# USBC.net
KiCad netlist of a schematic drawn in Altium Designer
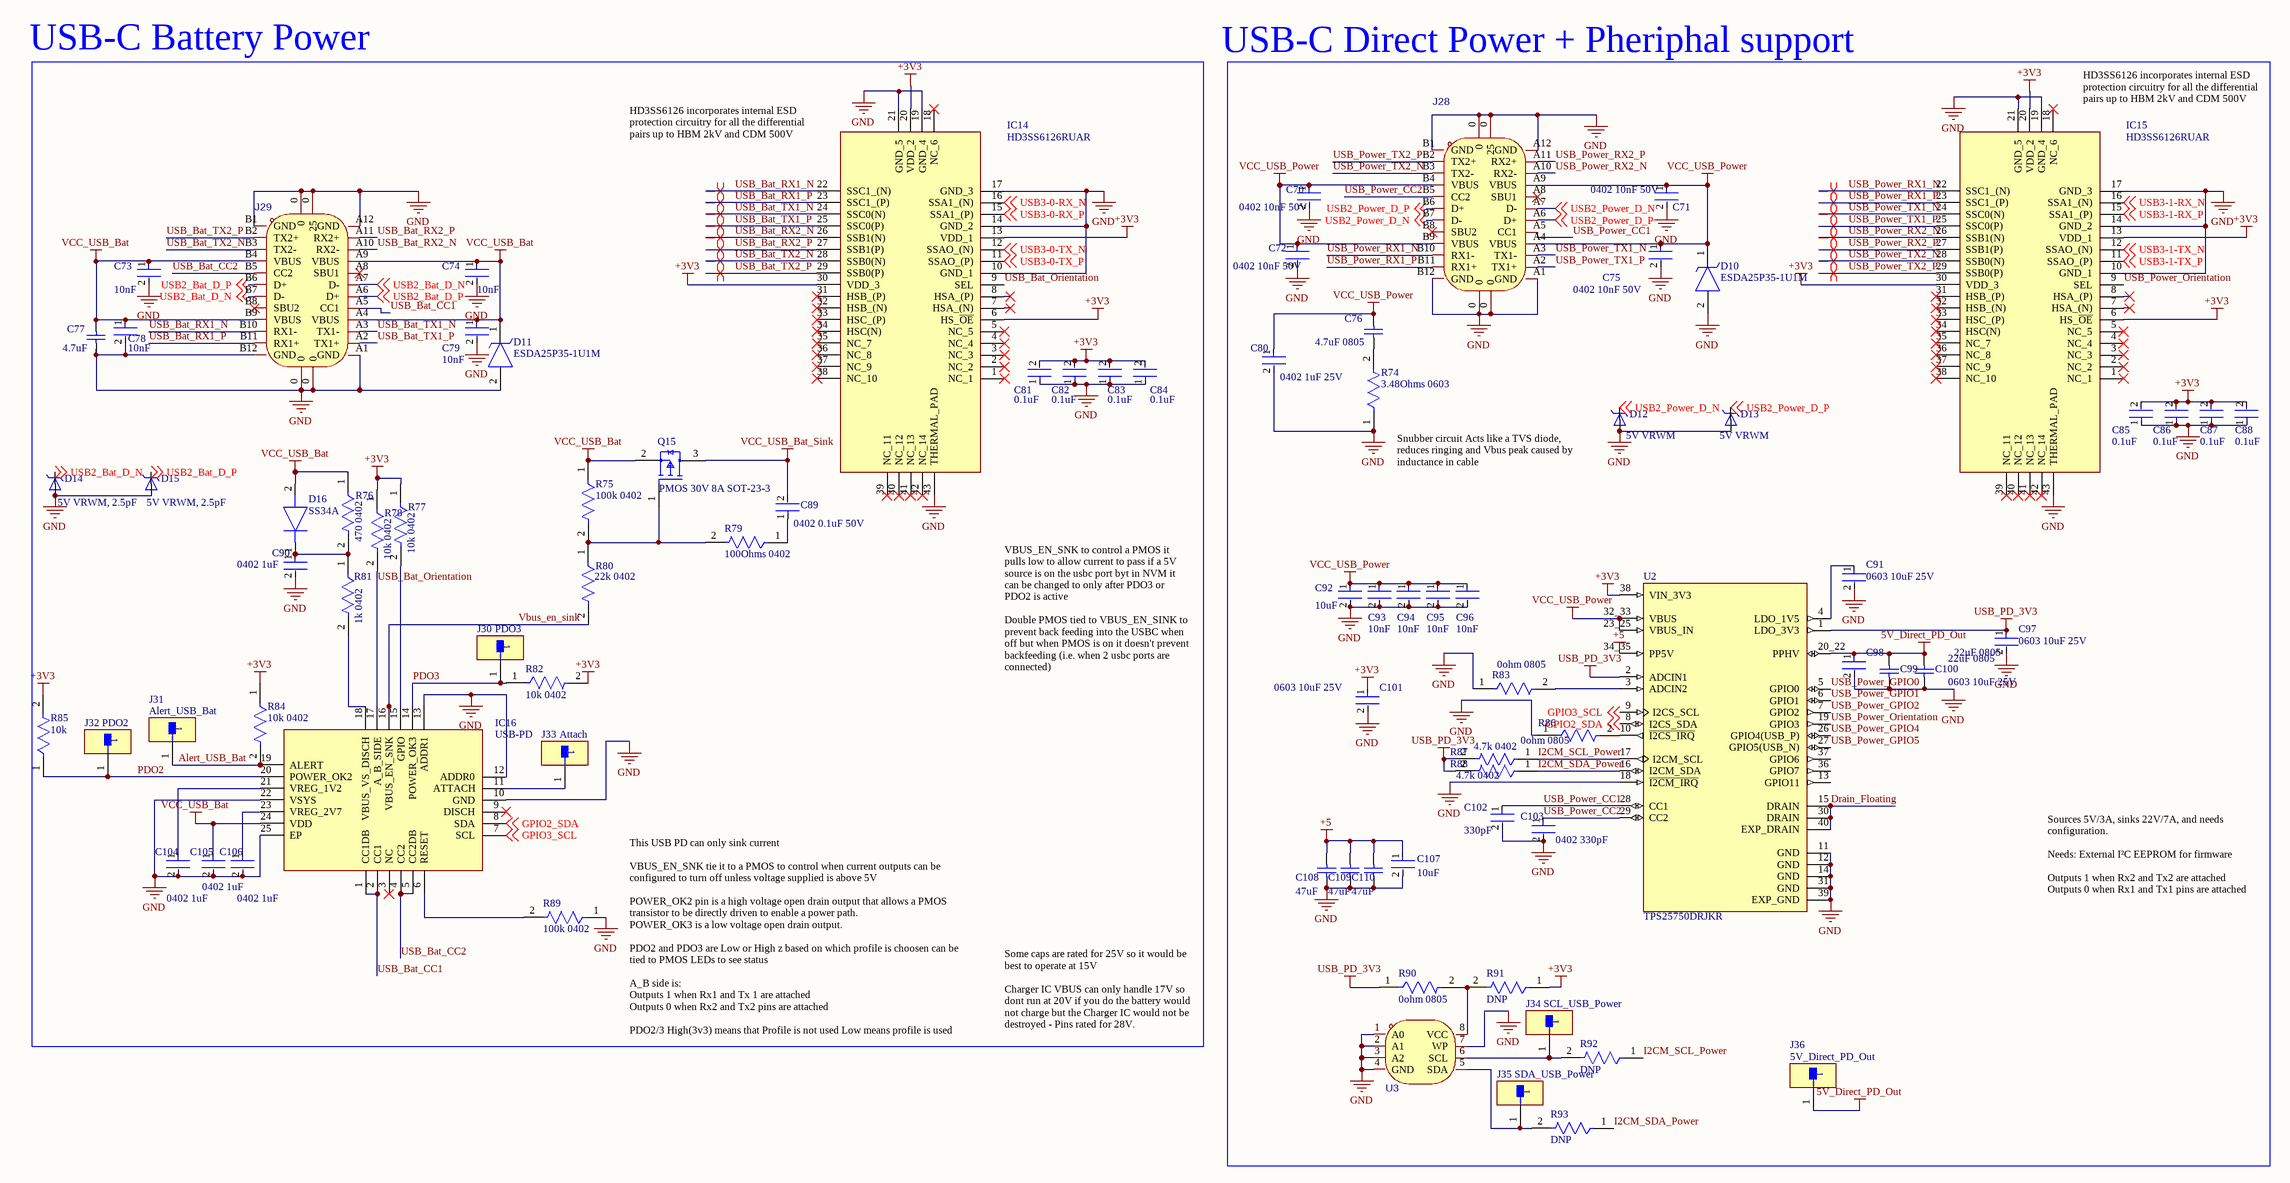
[diagram p0: USBC.SchDoc]

(export (version "E")
  (design (tool "Eeschema 10.0.6"))
  (components
    (comp (ref "C70")
      (value "0402 10nF 50V")
      (footprint "FP-C0402-BB-MFG")
      (description "C15195")
      (fields
        (field (name "TOLERANCE") "0.2")
        (field (name "OCTOPART") "https://octopart.com/c0402c104m3pac7867-kemet-84304880")
      )
      (libsource (lib "Altium Content Vault") (part "b4654b650e69147ec39a6b967a45e02"))
    )
    (comp (ref "C71")
      (value "0402 10nF 50V")
      (footprint "FP-C0402-BB-MFG")
      (description "C15195")
      (fields
        (field (name "TOLERANCE") "0.2")
        (field (name "OCTOPART") "https://octopart.com/c0402c104m3pac7867-kemet-84304880")
      )
      (libsource (lib "Altium Content Vault") (part "b4654b650e69147ec39a6b967a45e02"))
    )
    (comp (ref "C72")
      (value "0402 10nF 50V")
      (footprint "FP-C0402-BB-MFG")
      (description "C15195")
      (fields
        (field (name "TOLERANCE") "0.2")
        (field (name "OCTOPART") "https://octopart.com/c0402c104m3pac7867-kemet-84304880")
      )
      (libsource (lib "Altium Content Vault") (part "b4654b650e69147ec39a6b967a45e02"))
    )
    (comp (ref "C73")
      (value "10nF")
      (footprint "FP-C0402-BB-MFG")
      (description "C15195")
      (fields
        (field (name "TOLERANCE") "0.2")
        (field (name "OCTOPART") "https://octopart.com/c0402c104m3pac7867-kemet-84304880")
      )
      (libsource (lib "Altium Content Vault") (part "b4654b650e69147ec39a6b967a45e02"))
    )
    (comp (ref "C74")
      (value "10nF")
      (footprint "FP-C0402-BB-MFG")
      (description "C15195")
      (fields
        (field (name "TOLERANCE") "0.2")
        (field (name "OCTOPART") "https://octopart.com/c0402c104m3pac7867-kemet-84304880")
      )
      (libsource (lib "Altium Content Vault") (part "b4654b650e69147ec39a6b967a45e02"))
    )
    (comp (ref "C75")
      (value "0402 10nF 50V")
      (footprint "FP-C0402-BB-MFG")
      (description "C15195")
      (fields
        (field (name "TOLERANCE") "0.2")
        (field (name "OCTOPART") "https://octopart.com/c0402c104m3pac7867-kemet-84304880")
      )
      (libsource (lib "Altium Content Vault") (part "b4654b650e69147ec39a6b967a45e02"))
    )
    (comp (ref "C76")
      (value "4.7uF 0805")
      (footprint "CAPC2013X145X50ML20T25")
      (description "C7472970")
      (fields (field (name "MANUFACTURER") "Kemet") (field (name "PART NUMBER") "C0805F223K5RACTU"))
      (libsource (lib "Altium Content Vault") (part "CAP"))
    )
    (comp (ref "C77")
      (value "4.7uF")
      (footprint "CAPC2013X145X50ML20T25")
      (description "C7472970")
      (fields (field (name "MANUFACTURER") "Kemet") (field (name "PART NUMBER") "C0805F223K5RACTU"))
      (libsource (lib "Altium Content Vault") (part "CAP"))
    )
    (comp (ref "C78")
      (value "10nF")
      (footprint "FP-C0402-BB-MFG")
      (description "C15195")
      (fields
        (field (name "TOLERANCE") "0.2")
        (field (name "OCTOPART") "https://octopart.com/c0402c104m3pac7867-kemet-84304880")
      )
      (libsource (lib "Altium Content Vault") (part "b4654b650e69147ec39a6b967a45e02"))
    )
    (comp (ref "C79")
      (value "10nF")
      (footprint "FP-C0402-BB-MFG")
      (description "C15195")
      (fields
        (field (name "TOLERANCE") "0.2")
        (field (name "OCTOPART") "https://octopart.com/c0402c104m3pac7867-kemet-84304880")
      )
      (libsource (lib "Altium Content Vault") (part "b4654b650e69147ec39a6b967a45e02"))
    )
    (comp (ref "C80")
      (value "0402 1uF 25V")
      (footprint "FP-C0402-BB-MFG")
      (description "C52923")
      (fields
        (field (name "TOLERANCE") "0.2")
        (field (name "OCTOPART") "https://octopart.com/c0402c104m3pac7867-kemet-84304880")
      )
      (libsource (lib "Altium Content Vault") (part "b4654b650e69147ec39a6b967a45e02"))
    )
    (comp (ref "C81")
      (value "0.1uF")
      (footprint "FP-C0402-BB-MFG")
      (description "C307331")
      (fields
        (field (name "TOLERANCE") "0.2")
        (field (name "OCTOPART") "https://octopart.com/c0402c104m3pac7867-kemet-84304880")
      )
      (libsource (lib "Altium Content Vault") (part "b4654b650e69147ec39a6b967a45e02"))
    )
    (comp (ref "C82")
      (value "0.1uF")
      (footprint "FP-C0402-BB-MFG")
      (description "C307331")
      (fields
        (field (name "TOLERANCE") "0.2")
        (field (name "OCTOPART") "https://octopart.com/c0402c104m3pac7867-kemet-84304880")
      )
      (libsource (lib "Altium Content Vault") (part "b4654b650e69147ec39a6b967a45e02"))
    )
    (comp (ref "C83")
      (value "0.1uF")
      (footprint "FP-C0402-BB-MFG")
      (description "C307331")
      (fields
        (field (name "TOLERANCE") "0.2")
        (field (name "OCTOPART") "https://octopart.com/c0402c104m3pac7867-kemet-84304880")
      )
      (libsource (lib "Altium Content Vault") (part "b4654b650e69147ec39a6b967a45e02"))
    )
    (comp (ref "C84")
      (value "0.1uF")
      (footprint "FP-C0402-BB-MFG")
      (description "C307331")
      (fields
        (field (name "TOLERANCE") "0.2")
        (field (name "OCTOPART") "https://octopart.com/c0402c104m3pac7867-kemet-84304880")
      )
      (libsource (lib "Altium Content Vault") (part "b4654b650e69147ec39a6b967a45e02"))
    )
    (comp (ref "C85")
      (value "0.1uF")
      (footprint "FP-C0402-BB-MFG")
      (description "C307331")
      (fields
        (field (name "TOLERANCE") "0.2")
        (field (name "OCTOPART") "https://octopart.com/c0402c104m3pac7867-kemet-84304880")
      )
      (libsource (lib "Altium Content Vault") (part "b4654b650e69147ec39a6b967a45e02"))
    )
    (comp (ref "C86")
      (value "0.1uF")
      (footprint "FP-C0402-BB-MFG")
      (description "C307331")
      (fields
        (field (name "TOLERANCE") "0.2")
        (field (name "OCTOPART") "https://octopart.com/c0402c104m3pac7867-kemet-84304880")
      )
      (libsource (lib "Altium Content Vault") (part "b4654b650e69147ec39a6b967a45e02"))
    )
    (comp (ref "C87")
      (value "0.1uF")
      (footprint "FP-C0402-BB-MFG")
      (description "C307331")
      (fields
        (field (name "TOLERANCE") "0.2")
        (field (name "OCTOPART") "https://octopart.com/c0402c104m3pac7867-kemet-84304880")
      )
      (libsource (lib "Altium Content Vault") (part "b4654b650e69147ec39a6b967a45e02"))
    )
    (comp (ref "C88")
      (value "0.1uF")
      (footprint "FP-C0402-BB-MFG")
      (description "C307331")
      (fields
        (field (name "TOLERANCE") "0.2")
        (field (name "OCTOPART") "https://octopart.com/c0402c104m3pac7867-kemet-84304880")
      )
      (libsource (lib "Altium Content Vault") (part "b4654b650e69147ec39a6b967a45e02"))
    )
    (comp (ref "C89")
      (value "0402 0.1uF 50V")
      (footprint "FP-C0402-BB-MFG")
      (description "C307331")
      (fields
        (field (name "TOLERANCE") "0.2")
        (field (name "OCTOPART") "https://octopart.com/c0402c104m3pac7867-kemet-84304880")
      )
      (libsource (lib "Altium Content Vault") (part "b4654b650e69147ec39a6b967a45e02"))
    )
    (comp (ref "C90")
      (value "0402 1uF")
      (footprint "FP-C0402-BB-MFG")
      (description "C52923")
      (fields
        (field (name "TOLERANCE") "0.2")
        (field (name "OCTOPART") "https://octopart.com/c0402c104m3pac7867-kemet-84304880")
      )
      (libsource (lib "Altium Content Vault") (part "b4654b650e69147ec39a6b967a45e02"))
    )
    (comp (ref "C91")
      (value "0603 10uF 25V")
      (footprint "FP-CC0603-DC-MFG")
      (description "C96446")
      (fields (field (name "TOLERANCE") "10%"))
      (libsource (lib "Altium Content Vault") (part "b4654b650e69147ec39a6b967a45e02"))
    )
    (comp (ref "C92")
      (value "10uF")
      (footprint "FP-CC0603-DC-MFG")
      (description "C96446")
      (fields (field (name "TOLERANCE") "10%"))
      (libsource (lib "Altium Content Vault") (part "b4654b650e69147ec39a6b967a45e02"))
    )
    (comp (ref "C93")
      (value "10nF")
      (footprint "FP-C0402-BB-MFG")
      (description "C15195")
      (fields
        (field (name "TOLERANCE") "0.2")
        (field (name "OCTOPART") "https://octopart.com/c0402c104m3pac7867-kemet-84304880")
      )
      (libsource (lib "Altium Content Vault") (part "b4654b650e69147ec39a6b967a45e02"))
    )
    (comp (ref "C94")
      (value "10nF")
      (footprint "FP-C0402-BB-MFG")
      (description "C15195")
      (fields
        (field (name "TOLERANCE") "0.2")
        (field (name "OCTOPART") "https://octopart.com/c0402c104m3pac7867-kemet-84304880")
      )
      (libsource (lib "Altium Content Vault") (part "b4654b650e69147ec39a6b967a45e02"))
    )
    (comp (ref "C95")
      (value "10nF")
      (footprint "FP-C0402-BB-MFG")
      (description "C15195")
      (fields
        (field (name "TOLERANCE") "0.2")
        (field (name "OCTOPART") "https://octopart.com/c0402c104m3pac7867-kemet-84304880")
      )
      (libsource (lib "Altium Content Vault") (part "b4654b650e69147ec39a6b967a45e02"))
    )
    (comp (ref "C96")
      (value "10nF")
      (footprint "FP-C0402-BB-MFG")
      (description "C15195")
      (fields
        (field (name "TOLERANCE") "0.2")
        (field (name "OCTOPART") "https://octopart.com/c0402c104m3pac7867-kemet-84304880")
      )
      (libsource (lib "Altium Content Vault") (part "b4654b650e69147ec39a6b967a45e02"))
    )
    (comp (ref "C97")
      (value "0603 10uF 25V")
      (footprint "FP-CC0603-DC-MFG")
      (description "C96446")
      (fields (field (name "TOLERANCE") "10%"))
      (libsource (lib "Altium Content Vault") (part "b4654b650e69147ec39a6b967a45e02"))
    )
    (comp (ref "C98")
      (value "0603 10uF 25V")
      (footprint "FP-CC0603-DC-MFG")
      (description "C96446")
      (fields (field (name "TOLERANCE") "10%"))
      (libsource (lib "Altium Content Vault") (part "b4654b650e69147ec39a6b967a45e02"))
    )
    (comp (ref "C99")
      (value "22uF 0805")
      (footprint "CAPC2013X94X50LL20T25")
      (description "C45783")
      (fields
        (field (name "PART NUMBER") "08051C102KAT4A")
        (field (name "MANUFACTURER") "AVX Interconnect / Elco")
      )
      (libsource (lib "Altium Content Vault") (part "CAP"))
    )
    (comp (ref "C100")
      (value "22uF 0805")
      (footprint "CAPC2013X94X50LL20T25")
      (description "C45783")
      (fields
        (field (name "PART NUMBER") "08051C102KAT4A")
        (field (name "MANUFACTURER") "AVX Interconnect / Elco")
      )
      (libsource (lib "Altium Content Vault") (part "CAP"))
    )
    (comp (ref "C101")
      (value "0603 10uF 25V")
      (footprint "FP-CC0603-DC-MFG")
      (description "C96446")
      (fields (field (name "TOLERANCE") "10%"))
      (libsource (lib "Altium Content Vault") (part "b4654b650e69147ec39a6b967a45e02"))
    )
    (comp (ref "C102")
      (value "330pF")
      (footprint "FP-C0402-BB-MFG")
      (description "C13533")
      (fields
        (field (name "TOLERANCE") "0.2")
        (field (name "OCTOPART") "https://octopart.com/c0402c104m3pac7867-kemet-84304880")
      )
      (libsource (lib "Altium Content Vault") (part "b4654b650e69147ec39a6b967a45e02"))
    )
    (comp (ref "C103")
      (value "0402 330pF")
      (footprint "FP-C0402-BB-MFG")
      (description "C13533")
      (fields
        (field (name "TOLERANCE") "0.2")
        (field (name "OCTOPART") "https://octopart.com/c0402c104m3pac7867-kemet-84304880")
      )
      (libsource (lib "Altium Content Vault") (part "b4654b650e69147ec39a6b967a45e02"))
    )
    (comp (ref "C104")
      (value "0402 1uF")
      (footprint "FP-C0402-BB-MFG")
      (description "C52923")
      (fields
        (field (name "TOLERANCE") "0.2")
        (field (name "OCTOPART") "https://octopart.com/c0402c104m3pac7867-kemet-84304880")
      )
      (libsource (lib "Altium Content Vault") (part "b4654b650e69147ec39a6b967a45e02"))
    )
    (comp (ref "C105")
      (value "0402 1uF")
      (footprint "FP-C0402-BB-MFG")
      (description "C52923")
      (fields
        (field (name "TOLERANCE") "0.2")
        (field (name "OCTOPART") "https://octopart.com/c0402c104m3pac7867-kemet-84304880")
      )
      (libsource (lib "Altium Content Vault") (part "b4654b650e69147ec39a6b967a45e02"))
    )
    (comp (ref "C106")
      (value "0402 1uF")
      (footprint "FP-C0402-BB-MFG")
      (description "C52923")
      (fields
        (field (name "TOLERANCE") "0.2")
        (field (name "OCTOPART") "https://octopart.com/c0402c104m3pac7867-kemet-84304880")
      )
      (libsource (lib "Altium Content Vault") (part "b4654b650e69147ec39a6b967a45e02"))
    )
    (comp (ref "C107")
      (value "10uF")
      (footprint "FP-CC0603-DC-MFG")
      (description "C96446")
      (fields (field (name "TOLERANCE") "10%"))
      (libsource (lib "Altium Content Vault") (part "b4654b650e69147ec39a6b967a45e02"))
    )
    (comp (ref "C108")
      (value "47uF")
      (footprint "CAPC1206(3216)100_N")
      (description "C7472975")
      (fields (field (name "TOLERANCE") "Â±1%"))
      (libsource (lib "Altium Content Vault") (part "CAP"))
    )
    (comp (ref "C109")
      (value "47uF")
      (footprint "CAPC1206(3216)100_N")
      (description "C7472975")
      (fields (field (name "TOLERANCE") "Â±1%"))
      (libsource (lib "Altium Content Vault") (part "CAP"))
    )
    (comp (ref "C110")
      (value "47uF")
      (footprint "CAPC1206(3216)100_N")
      (description "C7472975")
      (fields (field (name "TOLERANCE") "Â±1%"))
      (libsource (lib "Altium Content Vault") (part "CAP"))
    )
    (comp (ref "D10")
      (value "ESDA25P35-1U1M")
      (footprint "PcbLib1:ESDA25P351U1M")
      (description "C1974707")
      (fields (field (name "MOUSER PART NUMBER") "511-ESDA25P35-1U1M"))
      (libsource (lib "*") (part "ESDA25P35-1U1M"))
    )
    (comp (ref "D11")
      (value "ESDA25P35-1U1M")
      (footprint "PcbLib1:ESDA25P351U1M")
      (description "C1974707")
      (fields (field (name "MOUSER PART NUMBER") "511-ESDA25P35-1U1M"))
      (libsource (lib "*") (part "ESDA25P35-1U1M"))
    )
    (comp (ref "D12")
      (value "5V VRWM")
      (footprint "PcbLib1:SODFL1060X40N")
      (description "C242267")
      (fields (field (name "MF") "ON Semiconductor") (field (name "MP") "ESD9M5.0ST5G"))
      (libsource (lib "Schlib1") (part "ESD9M5.0ST5G"))
    )
    (comp (ref "D13")
      (value "5V VRWM")
      (footprint "PcbLib1:SODFL1060X40N")
      (description "C242267")
      (fields (field (name "MF") "ON Semiconductor") (field (name "MP") "ESD9M5.0ST5G"))
      (libsource (lib "Schlib1") (part "ESD9M5.0ST5G"))
    )
    (comp (ref "D14")
      (value "5V VRWM, 2.5pF")
      (footprint "PcbLib1:SODFL1060X40N")
      (description "C242267")
      (fields (field (name "MF") "ON Semiconductor") (field (name "MP") "ESD9M5.0ST5G"))
      (libsource (lib "Schlib1") (part "ESD9M5.0ST5G"))
    )
    (comp (ref "D15")
      (value "5V VRWM, 2.5pF")
      (footprint "PcbLib1:SODFL1060X40N")
      (description "C242267")
      (fields (field (name "MF") "ON Semiconductor") (field (name "MP") "ESD9M5.0ST5G"))
      (libsource (lib "Schlib1") (part "ESD9M5.0ST5G"))
    )
    (comp (ref "D16")
      (value "SS34A")
      (footprint "SamacSys:DIOM5026X262N")
      (description "C8678")
      (libsource (lib "*") (part "SS34A"))
    )
    (comp (ref "IC14")
      (value "HD3SS6126RUAR")
      (footprint "PcbLib1:QFN50P350X900X80-43N-D")
      (description "C701818")
      (fields (field (name "MOUSER PART NUMBER") "595-HD3SS6126RUAR"))
      (libsource (lib "*") (part "HD3SS6126RUAR"))
    )
    (comp (ref "IC15")
      (value "HD3SS6126RUAR")
      (footprint "PcbLib1:QFN50P350X900X80-43N-D")
      (description "C701818")
      (fields (field (name "MOUSER PART NUMBER") "595-HD3SS6126RUAR"))
      (libsource (lib "*") (part "HD3SS6126RUAR"))
    )
    (comp (ref "IC16")
      (value "USB-PD")
      (footprint "PcbLib1:QFN50P400X400X100-25N-D")
      (description "C2678061")
      (fields
        (field (name "MANUFACTURER_PART_NUMBER") "STUSB4500QTR")
        (field (name "MOUSER PART NUMBER") "511-STUSB4500QTR")
      )
      (libsource (lib "Schlib1") (part "STUSB4500QTR"))
    )
    (comp (ref "J28")
      (value "1054500101")
      (footprint "USB-C-SMD_TYPE-C-USB-18")
      (description "C134092")
      (fields (field (name "MANUFACTURER") "MOLEX"))
      (libsource (lib "Schlib1") (part "1054500101"))
    )
    (comp (ref "J29")
      (value "1054500101")
      (footprint "USB-C-SMD_TYPE-C-USB-18")
      (description "C134092")
      (fields (field (name "MANUFACTURER") "MOLEX"))
      (libsource (lib "Schlib1") (part "1054500101"))
    )
    (comp (ref "J30")
      (value "PDO3")
      (footprint "FP-5015-MFG")
      (description "PC TEST POINT MINIATURE")
      (fields (field (name "MANUFACTURER PART NUMBER") "5015") (field (name "MANUFACTURER") "keystone"))
      (libsource (lib "Altium Content Vault") (part "dd45045ce8184df9e99e12baf3f412c"))
    )
    (comp (ref "J31")
      (value "Alert_USB_Bat")
      (footprint "FP-5015-MFG")
      (description "PC TEST POINT MINIATURE")
      (fields (field (name "MANUFACTURER PART NUMBER") "5015") (field (name "MANUFACTURER") "keystone"))
      (libsource (lib "Altium Content Vault") (part "dd45045ce8184df9e99e12baf3f412c"))
    )
    (comp (ref "J32")
      (value "PDO2")
      (footprint "FP-5015-MFG")
      (description "PC TEST POINT MINIATURE")
      (fields (field (name "MANUFACTURER PART NUMBER") "5015") (field (name "MANUFACTURER") "keystone"))
      (libsource (lib "Altium Content Vault") (part "dd45045ce8184df9e99e12baf3f412c"))
    )
    (comp (ref "J33")
      (value "Attach")
      (footprint "FP-5015-MFG")
      (description "PC TEST POINT MINIATURE")
      (fields (field (name "MANUFACTURER PART NUMBER") "5015") (field (name "MANUFACTURER") "keystone"))
      (libsource (lib "Altium Content Vault") (part "dd45045ce8184df9e99e12baf3f412c"))
    )
    (comp (ref "J34")
      (value "SCL_USB_Power")
      (footprint "FP-TSW-101-07-L-S-MFG")
      (description "CONN HEADER VERT 1POS")
      (libsource (lib "Altium Content Vault") (part "dd45045ce8184df9e99e12baf3f412c"))
    )
    (comp (ref "J35")
      (value "SDA_USB_Power")
      (footprint "FP-TSW-101-07-L-S-MFG")
      (description "CONN HEADER VERT 1POS")
      (libsource (lib "Altium Content Vault") (part "dd45045ce8184df9e99e12baf3f412c"))
    )
    (comp (ref "J36")
      (value "5V_Direct_PD_Out")
      (footprint "FP-5015-MFG")
      (description "PC TEST POINT MINIATURE")
      (fields (field (name "MANUFACTURER PART NUMBER") "5015") (field (name "MANUFACTURER") "keystone"))
      (libsource (lib "Altium Content Vault") (part "dd45045ce8184df9e99e12baf3f412c"))
    )
    (comp (ref "Q15")
      (value "PMOS 30V 8A SOT-23-3")
      (footprint "FP-SOT23-MFG")
      (description "C48934562")
      (fields
        (field (name "MANUFACTURER") "Diodes Inc.")
        (field (name "MANUFACTURER PART NUMBER") "DMG2305UX-13")
      )
      (libsource (lib "Altium Content Vault") (part "b298ed0aef6ca29edb293456b19cad3"))
    )
    (comp (ref "R74")
      (value "3.48Ohms 0603")
      (footprint "FP-RMCF0603-IPC_A")
      (description "C322150")
      (fields (field (name "TOLERANCE") "1%"))
      (libsource (lib "Altium Content Vault") (part "1029c3af85768c4190bb7ad29bc67b5"))
    )
    (comp (ref "R75")
      (value "100k 0402")
      (footprint "FP-RMCF0402-MFG")
      (description "C25741")
      (fields (field (name "TOLERANCE") "5%"))
      (libsource (lib "Altium Content Vault") (part "1029c3af85768c4190bb7ad29bc67b5"))
    )
    (comp (ref "R76")
      (value "470 0402")
      (footprint "FP-RMCF0402-MFG")
      (description "C25117")
      (fields (field (name "TOLERANCE") "5%"))
      (libsource (lib "Altium Content Vault") (part "1029c3af85768c4190bb7ad29bc67b5"))
    )
    (comp (ref "R77")
      (value "10k 0402")
      (footprint "FP-RMCF0402-MFG")
      (description "C25744")
      (fields (field (name "TOLERANCE") "5%"))
      (libsource (lib "Altium Content Vault") (part "1029c3af85768c4190bb7ad29bc67b5"))
    )
    (comp (ref "R78")
      (value "10k 0402")
      (footprint "FP-RMCF0402-MFG")
      (description "C25744")
      (fields (field (name "TOLERANCE") "5%"))
      (libsource (lib "Altium Content Vault") (part "1029c3af85768c4190bb7ad29bc67b5"))
    )
    (comp (ref "R79")
      (value "100Ohms 0402")
      (footprint "FP-RMCF0402-MFG")
      (description "C25076")
      (fields (field (name "TOLERANCE") "5%"))
      (libsource (lib "Altium Content Vault") (part "1029c3af85768c4190bb7ad29bc67b5"))
    )
    (comp (ref "R80")
      (value "22k 0402")
      (footprint "FP-RMCF0402-MFG")
      (description "C25768")
      (fields (field (name "TOLERANCE") "5%"))
      (libsource (lib "Altium Content Vault") (part "1029c3af85768c4190bb7ad29bc67b5"))
    )
    (comp (ref "R81")
      (value "1k 0402")
      (footprint "FP-RMCF0402-MFG")
      (description "C11702")
      (fields (field (name "TOLERANCE") "5%"))
      (libsource (lib "Altium Content Vault") (part "1029c3af85768c4190bb7ad29bc67b5"))
    )
    (comp (ref "R82")
      (value "10k 0402")
      (footprint "FP-RMCF0402-MFG")
      (description "C25744")
      (fields (field (name "TOLERANCE") "5%"))
      (libsource (lib "Altium Content Vault") (part "1029c3af85768c4190bb7ad29bc67b5"))
    )
    (comp (ref "R83")
      (value "0ohm 0805")
      (footprint "FP-RN73R2A-IPC_C")
      (description "C17477")
      (libsource (lib "Altium Content Vault") (part "1029c3af85768c4190bb7ad29bc67b5"))
    )
    (comp (ref "R84")
      (value "10k 0402")
      (footprint "FP-RMCF0402-MFG")
      (description "C25744")
      (fields (field (name "TOLERANCE") "5%"))
      (libsource (lib "Altium Content Vault") (part "1029c3af85768c4190bb7ad29bc67b5"))
    )
    (comp (ref "R85")
      (value "10k")
      (footprint "FP-RMCF0402-MFG")
      (description "C25744")
      (fields (field (name "TOLERANCE") "5%"))
      (libsource (lib "Altium Content Vault") (part "1029c3af85768c4190bb7ad29bc67b5"))
    )
    (comp (ref "R86")
      (value "0ohm 0805")
      (footprint "FP-RN73R2A-IPC_C")
      (description "C17477")
      (libsource (lib "Altium Content Vault") (part "1029c3af85768c4190bb7ad29bc67b5"))
    )
    (comp (ref "R87")
      (value "4.7k 0402")
      (footprint "FP-RMCF0402-MFG")
      (description "C25900")
      (fields (field (name "TOLERANCE") "5%"))
      (libsource (lib "Altium Content Vault") (part "1029c3af85768c4190bb7ad29bc67b5"))
    )
    (comp (ref "R88")
      (value "4.7k 0402")
      (footprint "FP-RMCF0402-MFG")
      (description "C25900")
      (fields (field (name "TOLERANCE") "5%"))
      (libsource (lib "Altium Content Vault") (part "1029c3af85768c4190bb7ad29bc67b5"))
    )
    (comp (ref "R89")
      (value "100k 0402")
      (footprint "FP-RMCF0402-MFG")
      (description "C25741")
      (fields (field (name "TOLERANCE") "5%"))
      (libsource (lib "Altium Content Vault") (part "1029c3af85768c4190bb7ad29bc67b5"))
    )
    (comp (ref "R90")
      (value "0ohm 0805")
      (footprint "FP-RN73R2A-IPC_C")
      (description "C17477")
      (libsource (lib "Altium Content Vault") (part "1029c3af85768c4190bb7ad29bc67b5"))
    )
    (comp (ref "R91")
      (value "DNP")
      (footprint "FP-RN73R2A-IPC_C")
      (description "DNP 0805")
      (libsource (lib "Altium Content Vault") (part "1029c3af85768c4190bb7ad29bc67b5"))
    )
    (comp (ref "R92")
      (value "DNP")
      (footprint "FP-RN73R2A-IPC_C")
      (description "DNP 0805")
      (libsource (lib "Altium Content Vault") (part "1029c3af85768c4190bb7ad29bc67b5"))
    )
    (comp (ref "R93")
      (value "DNP")
      (footprint "FP-RN73R2A-IPC_C")
      (description "DNP 0805")
      (libsource (lib "Altium Content Vault") (part "1029c3af85768c4190bb7ad29bc67b5"))
    )
    (comp (ref "U2")
      (value "TPS25750DRJKR")
      (footprint "IC_TPS25750DRJKR")
      (description "C2868209")
      (fields (field (name "MF") "Texas Instruments"))
      (libsource (lib "Schlib1") (part "TPS25750DRJKR"))
    )
    (comp (ref "U3")
      (value "BL24C256A-SFRC")
      (footprint "TSSOP-8_L4.4-W3.0-P0.65-LS6.4-BL")
      (description "C110276")
      (fields (field (name "MANUFACTURER") "BL(上海贝岭)"))
      (libsource (lib "Schlib1") (part "BL24C256A-SFRC"))
    )
  )
  (nets
    (net (code "1") (name "+3V3") (class "Default")
      (node (ref "C101") (pin "1") (pinfunction "1_1") (pintype "passive"))
      (node (ref "C81") (pin "2") (pinfunction "2_2") (pintype "passive"))
      (node (ref "C82") (pin "2") (pinfunction "2_2") (pintype "passive"))
      (node (ref "C83") (pin "2") (pinfunction "2_2") (pintype "passive"))
      (node (ref "C84") (pin "2") (pinfunction "2_2") (pintype "passive"))
      (node (ref "C85") (pin "2") (pinfunction "2_2") (pintype "passive"))
      (node (ref "C86") (pin "2") (pinfunction "2_2") (pintype "passive"))
      (node (ref "C87") (pin "2") (pinfunction "2_2") (pintype "passive"))
      (node (ref "C88") (pin "2") (pinfunction "2_2") (pintype "passive"))
      (node (ref "IC14") (pin "13") (pinfunction "VDD_1_13") (pintype "passive"))
      (node (ref "IC14") (pin "20") (pinfunction "VDD_2_20") (pintype "passive"))
      (node (ref "IC14") (pin "30") (pinfunction "VDD_3_30") (pintype "passive"))
      (node (ref "IC14") (pin "6") (pinfunction "HS_~{OE}_6") (pintype "passive"))
      (node (ref "IC15") (pin "13") (pinfunction "VDD_1_13") (pintype "passive"))
      (node (ref "IC15") (pin "20") (pinfunction "VDD_2_20") (pintype "passive"))
      (node (ref "IC15") (pin "30") (pinfunction "VDD_3_30") (pintype "passive"))
      (node (ref "IC15") (pin "6") (pinfunction "HS_~{OE}_6") (pintype "passive"))
      (node (ref "R77") (pin "1") (pinfunction "1_1") (pintype "passive"))
      (node (ref "R78") (pin "1") (pinfunction "1_1") (pintype "passive"))
      (node (ref "R82") (pin "2") (pinfunction "2_2") (pintype "passive"))
      (node (ref "R84") (pin "1") (pinfunction "1_1") (pintype "passive"))
      (node (ref "R85") (pin "2") (pinfunction "2_2") (pintype "passive"))
      (node (ref "R91") (pin "1") (pinfunction "1_1") (pintype "passive"))
      (node (ref "U2") (pin "38") (pinfunction "VIN_3V3_38") (pintype "input"))
    )
    (net (code "2") (name "+5") (class "Default")
      (node (ref "C107") (pin "1") (pinfunction "1_1") (pintype "passive"))
      (node (ref "C108") (pin "2") (pinfunction "2_2") (pintype "passive"))
      (node (ref "C109") (pin "2") (pinfunction "2_2") (pintype "passive"))
      (node (ref "C110") (pin "2") (pinfunction "2_2") (pintype "passive"))
      (node (ref "U2") (pin "34_35") (pinfunction "PP5V_34_35") (pintype "input"))
    )
    (net (code "3") (name "/Alert_USB_Bat") (class "Default")
      (node (ref "IC16") (pin "19") (pinfunction "ALERT_19") (pintype "passive"))
      (node (ref "J31") (pin "1") (pinfunction "1_1") (pintype "passive"))
      (node (ref "R84") (pin "2") (pinfunction "2_2") (pintype "passive"))
    )
    (net (code "4") (name "/Drain_Floating") (class "Default")
      (node (ref "U2") (pin "15") (pinfunction "DRAIN_15") (pintype "passive"))
      (node (ref "U2") (pin "30") (pinfunction "DRAIN_30") (pintype "passive"))
      (node (ref "U2") (pin "40") (pinfunction "EXP_DRAIN_40") (pintype "passive"))
    )
    (net (code "5") (name "/I2CM_SCL_Power") (class "Default")
      (node (ref "R87") (pin "1") (pinfunction "1_1") (pintype "passive"))
      (node (ref "R92") (pin "1") (pinfunction "1_1") (pintype "passive"))
      (node (ref "U2") (pin "17") (pinfunction "I2CM_SCL_17") (pintype "output"))
    )
    (net (code "6") (name "/I2CM_SDA_Power") (class "Default")
      (node (ref "R88") (pin "1") (pinfunction "1_1") (pintype "passive"))
      (node (ref "R93") (pin "1") (pinfunction "1_1") (pintype "passive"))
      (node (ref "U2") (pin "16") (pinfunction "I2CM_SDA_16") (pintype "bidirectional"))
    )
    (net (code "7") (name "/PDO2") (class "Default")
      (node (ref "IC16") (pin "20") (pinfunction "POWER_OK2_20") (pintype "passive"))
      (node (ref "J32") (pin "1") (pinfunction "1_1") (pintype "passive"))
      (node (ref "R85") (pin "1") (pinfunction "1_1") (pintype "passive"))
    )
    (net (code "8") (name "/PDO3") (class "Default")
      (node (ref "IC16") (pin "14") (pinfunction "POWER_OK3_14") (pintype "passive"))
      (node (ref "J30") (pin "1") (pinfunction "1_1") (pintype "passive"))
      (node (ref "R82") (pin "1") (pinfunction "1_1") (pintype "passive"))
    )
    (net (code "9") (name "/USB_Bat_CC1") (class "Default")
      (node (ref "IC16") (pin "1") (pinfunction "CC1DB_1") (pintype "passive"))
      (node (ref "IC16") (pin "2") (pinfunction "CC1_2") (pintype "passive"))
      (node (ref "J29") (pin "A5") (pinfunction "CC1_A5") (pintype "passive"))
    )
    (net (code "10") (name "/USB_Bat_CC2") (class "Default")
      (node (ref "IC16") (pin "4") (pinfunction "CC2_4") (pintype "passive"))
      (node (ref "IC16") (pin "5") (pinfunction "CC2DB_5") (pintype "passive"))
      (node (ref "J29") (pin "B5") (pinfunction "CC2_B5") (pintype "passive"))
    )
    (net (code "11") (name "/USB_Bat_Orientation") (class "Default")
      (node (ref "IC14") (pin "9") (pinfunction "SEL_9") (pintype "passive"))
      (node (ref "IC16") (pin "17") (pinfunction "A_B_SIDE_17") (pintype "passive"))
      (node (ref "R78") (pin "2") (pinfunction "2_2") (pintype "passive"))
    )
    (net (code "12") (name "/USB_Bat_RX1_N") (class "Default")
      (node (ref "IC14") (pin "22") (pinfunction "SSC1_(N)_22") (pintype "passive"))
      (node (ref "J29") (pin "B10") (pinfunction "RX1-_B10") (pintype "passive"))
    )
    (net (code "13") (name "/USB_Bat_RX1_P") (class "Default")
      (node (ref "IC14") (pin "23") (pinfunction "SSC1_(P)_23") (pintype "passive"))
      (node (ref "J29") (pin "B11") (pinfunction "RX1+_B11") (pintype "passive"))
    )
    (net (code "14") (name "/USB_Bat_RX2_N") (class "Default")
      (node (ref "IC14") (pin "26") (pinfunction "SSB1(N)_26") (pintype "passive"))
      (node (ref "J29") (pin "A10") (pinfunction "RX2-_A10") (pintype "passive"))
    )
    (net (code "15") (name "/USB_Bat_RX2_P") (class "Default")
      (node (ref "IC14") (pin "27") (pinfunction "SSB1(P)_27") (pintype "passive"))
      (node (ref "J29") (pin "A11") (pinfunction "RX2+_A11") (pintype "passive"))
    )
    (net (code "16") (name "/USB_Bat_TX1_N") (class "Default")
      (node (ref "IC14") (pin "24") (pinfunction "SSC0(N)_24") (pintype "passive"))
      (node (ref "J29") (pin "A3") (pinfunction "TX1-_A3") (pintype "passive"))
    )
    (net (code "17") (name "/USB_Bat_TX1_P") (class "Default")
      (node (ref "IC14") (pin "25") (pinfunction "SSC0(P)_25") (pintype "passive"))
      (node (ref "J29") (pin "A2") (pinfunction "TX1+_A2") (pintype "passive"))
    )
    (net (code "18") (name "/USB_Bat_TX2_N") (class "Default")
      (node (ref "IC14") (pin "28") (pinfunction "SSB0(N)_28") (pintype "passive"))
      (node (ref "J29") (pin "B3") (pinfunction "TX2-_B3") (pintype "passive"))
    )
    (net (code "19") (name "/USB_Bat_TX2_P") (class "Default")
      (node (ref "IC14") (pin "29") (pinfunction "SSB0(P)_29") (pintype "passive"))
      (node (ref "J29") (pin "B2") (pinfunction "TX2+_B2") (pintype "passive"))
    )
    (net (code "20") (name "/USB_Power_CC1") (class "Default")
      (node (ref "C102") (pin "1") (pinfunction "1_1") (pintype "passive"))
      (node (ref "J28") (pin "A5") (pinfunction "CC1_A5") (pintype "passive"))
      (node (ref "U2") (pin "28") (pinfunction "CC1_28") (pintype "bidirectional"))
    )
    (net (code "21") (name "/USB_Power_CC2") (class "Default")
      (node (ref "C103") (pin "1") (pinfunction "1_1") (pintype "passive"))
      (node (ref "J28") (pin "B5") (pinfunction "CC2_B5") (pintype "passive"))
      (node (ref "U2") (pin "29") (pinfunction "CC2_29") (pintype "bidirectional"))
    )
    (net (code "22") (name "/USB_Power_GPIO0") (class "Default")
      (node (ref "U2") (pin "5") (pinfunction "GPIO0_5") (pintype "bidirectional"))
    )
    (net (code "23") (name "/USB_Power_GPIO1") (class "Default")
      (node (ref "U2") (pin "6") (pinfunction "GPIO1_6") (pintype "bidirectional"))
    )
    (net (code "24") (name "/USB_Power_GPIO2") (class "Default")
      (node (ref "U2") (pin "7") (pinfunction "GPIO2_7") (pintype "output"))
    )
    (net (code "25") (name "/USB_Power_GPIO4") (class "Default")
      (node (ref "U2") (pin "26") (pinfunction "GPIO4(USB_P)_26") (pintype "bidirectional"))
    )
    (net (code "26") (name "/USB_Power_GPIO5") (class "Default")
      (node (ref "U2") (pin "27") (pinfunction "GPIO5(USB_N)_27") (pintype "bidirectional"))
    )
    (net (code "27") (name "/USB_Power_Orientation") (class "Default")
      (node (ref "IC15") (pin "9") (pinfunction "SEL_9") (pintype "passive"))
      (node (ref "U2") (pin "19") (pinfunction "GPIO3_19") (pintype "output"))
    )
    (net (code "28") (name "/USB_Power_RX1_N") (class "Default")
      (node (ref "IC15") (pin "22") (pinfunction "SSC1_(N)_22") (pintype "passive"))
      (node (ref "J28") (pin "B10") (pinfunction "RX1-_B10") (pintype "passive"))
    )
    (net (code "29") (name "/USB_Power_RX1_P") (class "Default")
      (node (ref "IC15") (pin "23") (pinfunction "SSC1_(P)_23") (pintype "passive"))
      (node (ref "J28") (pin "B11") (pinfunction "RX1+_B11") (pintype "passive"))
    )
    (net (code "30") (name "/USB_Power_RX2_N") (class "Default")
      (node (ref "IC15") (pin "26") (pinfunction "SSB1(N)_26") (pintype "passive"))
      (node (ref "J28") (pin "A10") (pinfunction "RX2-_A10") (pintype "passive"))
    )
    (net (code "31") (name "/USB_Power_RX2_P") (class "Default")
      (node (ref "IC15") (pin "27") (pinfunction "SSB1(P)_27") (pintype "passive"))
      (node (ref "J28") (pin "A11") (pinfunction "RX2+_A11") (pintype "passive"))
    )
    (net (code "32") (name "/USB_Power_TX1_N") (class "Default")
      (node (ref "IC15") (pin "24") (pinfunction "SSC0(N)_24") (pintype "passive"))
      (node (ref "J28") (pin "A3") (pinfunction "TX1-_A3") (pintype "passive"))
    )
    (net (code "33") (name "/USB_Power_TX1_P") (class "Default")
      (node (ref "IC15") (pin "25") (pinfunction "SSC0(P)_25") (pintype "passive"))
      (node (ref "J28") (pin "A2") (pinfunction "TX1+_A2") (pintype "passive"))
    )
    (net (code "34") (name "/USB_Power_TX2_N") (class "Default")
      (node (ref "IC15") (pin "28") (pinfunction "SSB0(N)_28") (pintype "passive"))
      (node (ref "J28") (pin "B3") (pinfunction "TX2-_B3") (pintype "passive"))
    )
    (net (code "35") (name "/USB_Power_TX2_P") (class "Default")
      (node (ref "IC15") (pin "29") (pinfunction "SSB0(P)_29") (pintype "passive"))
      (node (ref "J28") (pin "B2") (pinfunction "TX2+_B2") (pintype "passive"))
    )
    (net (code "36") (name "/Vbus_en_sink") (class "Default")
      (node (ref "IC16") (pin "16") (pinfunction "VBUS_EN_SNK_16") (pintype "passive"))
      (node (ref "R80") (pin "2") (pinfunction "2_2") (pintype "passive"))
    )
    (net (code "37") (name "5V_Direct_PD_Out") (class "Default")
      (node (ref "C100") (pin "1") (pinfunction "1_1") (pintype "passive"))
      (node (ref "C98") (pin "1") (pinfunction "1_1") (pintype "passive"))
      (node (ref "C99") (pin "1") (pinfunction "1_1") (pintype "passive"))
      (node (ref "J36") (pin "1") (pinfunction "1_1") (pintype "passive"))
      (node (ref "U2") (pin "20_22") (pinfunction "PPHV_20_22") (pintype "bidirectional"))
    )
    (net (code "38") (name "GND") (class "Default")
      (node (ref "C100") (pin "2") (pinfunction "2_2") (pintype "passive"))
      (node (ref "C101") (pin "2") (pinfunction "2_2") (pintype "passive"))
      (node (ref "C102") (pin "2") (pinfunction "2_2") (pintype "passive"))
      (node (ref "C103") (pin "2") (pinfunction "2_2") (pintype "passive"))
      (node (ref "C104") (pin "2") (pinfunction "2_2") (pintype "passive"))
      (node (ref "C105") (pin "2") (pinfunction "2_2") (pintype "passive"))
      (node (ref "C106") (pin "2") (pinfunction "2_2") (pintype "passive"))
      (node (ref "C107") (pin "2") (pinfunction "2_2") (pintype "passive"))
      (node (ref "C108") (pin "1") (pinfunction "1_1") (pintype "passive"))
      (node (ref "C109") (pin "1") (pinfunction "1_1") (pintype "passive"))
      (node (ref "C110") (pin "1") (pinfunction "1_1") (pintype "passive"))
      (node (ref "C70") (pin "2") (pinfunction "2_2") (pintype "passive"))
      (node (ref "C71") (pin "2") (pinfunction "2_2") (pintype "passive"))
      (node (ref "C72") (pin "2") (pinfunction "2_2") (pintype "passive"))
      (node (ref "C73") (pin "2") (pinfunction "2_2") (pintype "passive"))
      (node (ref "C74") (pin "2") (pinfunction "2_2") (pintype "passive"))
      (node (ref "C75") (pin "2") (pinfunction "2_2") (pintype "passive"))
      (node (ref "C77") (pin "1") (pinfunction "1_1") (pintype "passive"))
      (node (ref "C78") (pin "2") (pinfunction "2_2") (pintype "passive"))
      (node (ref "C79") (pin "2") (pinfunction "2_2") (pintype "passive"))
      (node (ref "C80") (pin "2") (pinfunction "2_2") (pintype "passive"))
      (node (ref "C81") (pin "1") (pinfunction "1_1") (pintype "passive"))
      (node (ref "C82") (pin "1") (pinfunction "1_1") (pintype "passive"))
      (node (ref "C83") (pin "1") (pinfunction "1_1") (pintype "passive"))
      (node (ref "C84") (pin "1") (pinfunction "1_1") (pintype "passive"))
      (node (ref "C85") (pin "1") (pinfunction "1_1") (pintype "passive"))
      (node (ref "C86") (pin "1") (pinfunction "1_1") (pintype "passive"))
      (node (ref "C87") (pin "1") (pinfunction "1_1") (pintype "passive"))
      (node (ref "C88") (pin "1") (pinfunction "1_1") (pintype "passive"))
      (node (ref "C90") (pin "2") (pinfunction "2_2") (pintype "passive"))
      (node (ref "C91") (pin "2") (pinfunction "2_2") (pintype "passive"))
      (node (ref "C92") (pin "2") (pinfunction "2_2") (pintype "passive"))
      (node (ref "C93") (pin "2") (pinfunction "2_2") (pintype "passive"))
      (node (ref "C94") (pin "2") (pinfunction "2_2") (pintype "passive"))
      (node (ref "C95") (pin "2") (pinfunction "2_2") (pintype "passive"))
      (node (ref "C96") (pin "2") (pinfunction "2_2") (pintype "passive"))
      (node (ref "C97") (pin "2") (pinfunction "2_2") (pintype "passive"))
      (node (ref "C98") (pin "2") (pinfunction "2_2") (pintype "passive"))
      (node (ref "C99") (pin "2") (pinfunction "2_2") (pintype "passive"))
      (node (ref "D10") (pin "2") (pinfunction "A_2") (pintype "passive"))
      (node (ref "D11") (pin "2") (pinfunction "A_2") (pintype "passive"))
      (node (ref "D12") (pin "2") (pinfunction "2_2") (pintype "passive"))
      (node (ref "D13") (pin "2") (pinfunction "2_2") (pintype "passive"))
      (node (ref "D14") (pin "2") (pinfunction "2_2") (pintype "passive"))
      (node (ref "D15") (pin "2") (pinfunction "2_2") (pintype "passive"))
      (node (ref "IC14") (pin "10") (pinfunction "GND_1_10") (pintype "passive"))
      (node (ref "IC14") (pin "14") (pinfunction "GND_2_14") (pintype "passive"))
      (node (ref "IC14") (pin "17") (pinfunction "GND_3_17") (pintype "passive"))
      (node (ref "IC14") (pin "19") (pinfunction "GND_4_19") (pintype "passive"))
      (node (ref "IC14") (pin "21") (pinfunction "GND_5_21") (pintype "passive"))
      (node (ref "IC14") (pin "43") (pinfunction "THERMAL_PAD_43") (pintype "passive"))
      (node (ref "IC15") (pin "10") (pinfunction "GND_1_10") (pintype "passive"))
      (node (ref "IC15") (pin "14") (pinfunction "GND_2_14") (pintype "passive"))
      (node (ref "IC15") (pin "17") (pinfunction "GND_3_17") (pintype "passive"))
      (node (ref "IC15") (pin "19") (pinfunction "GND_4_19") (pintype "passive"))
      (node (ref "IC15") (pin "21") (pinfunction "GND_5_21") (pintype "passive"))
      (node (ref "IC15") (pin "43") (pinfunction "THERMAL_PAD_43") (pintype "passive"))
      (node (ref "IC16") (pin "10") (pinfunction "GND_10") (pintype "passive"))
      (node (ref "IC16") (pin "12") (pinfunction "ADDR0_12") (pintype "passive"))
      (node (ref "IC16") (pin "13") (pinfunction "ADDR1_13") (pintype "passive"))
      (node (ref "IC16") (pin "22") (pinfunction "VSYS_22") (pintype "passive"))
      (node (ref "IC16") (pin "25") (pinfunction "EP_25") (pintype "passive"))
      (node (ref "J28") (pin "0") (pinfunction "0_0") (pintype "passive"))
      (node (ref "J28") (pin "A1") (pinfunction "GND_A1") (pintype "passive"))
      (node (ref "J28") (pin "A12") (pinfunction "GND_A12") (pintype "passive"))
      (node (ref "J28") (pin "B1") (pinfunction "GND_B1") (pintype "passive"))
      (node (ref "J28") (pin "B12") (pinfunction "GND_B12") (pintype "passive"))
      (node (ref "J29") (pin "0") (pinfunction "0_0") (pintype "passive"))
      (node (ref "J29") (pin "A1") (pinfunction "GND_A1") (pintype "passive"))
      (node (ref "J29") (pin "A12") (pinfunction "GND_A12") (pintype "passive"))
      (node (ref "J29") (pin "B1") (pinfunction "GND_B1") (pintype "passive"))
      (node (ref "J29") (pin "B12") (pinfunction "GND_B12") (pintype "passive"))
      (node (ref "R74") (pin "1") (pinfunction "1_1") (pintype "passive"))
      (node (ref "R83") (pin "1") (pinfunction "1_1") (pintype "passive"))
      (node (ref "R86") (pin "1") (pinfunction "1_1") (pintype "passive"))
      (node (ref "R89") (pin "1") (pinfunction "1_1") (pintype "passive"))
      (node (ref "U2") (pin "11") (pinfunction "GND_11") (pintype "power_in"))
      (node (ref "U2") (pin "12") (pinfunction "GND_12") (pintype "power_in"))
      (node (ref "U2") (pin "14") (pinfunction "GND_14") (pintype "power_in"))
      (node (ref "U2") (pin "18") (pinfunction "~{I2CM_IRQ}_18") (pintype "input"))
      (node (ref "U2") (pin "31") (pinfunction "GND_31") (pintype "power_in"))
      (node (ref "U2") (pin "39") (pinfunction "EXP_GND_39") (pintype "power_in"))
      (node (ref "U3") (pin "1") (pinfunction "A0_1") (pintype "passive"))
      (node (ref "U3") (pin "2") (pinfunction "A1_2") (pintype "passive"))
      (node (ref "U3") (pin "3") (pinfunction "A2_3") (pintype "passive"))
      (node (ref "U3") (pin "4") (pinfunction "GND_4") (pintype "passive"))
      (node (ref "U3") (pin "7") (pinfunction "WP_7") (pintype "passive"))
    )
    (net (code "39") (name "GPIO2_SDA") (class "Default")
      (node (ref "IC16") (pin "8") (pinfunction "SDA_8") (pintype "passive"))
      (node (ref "U2") (pin "8") (pinfunction "I2CS_SDA_8") (pintype "bidirectional"))
    )
    (net (code "40") (name "GPIO3_SCL") (class "Default")
      (node (ref "IC16") (pin "7") (pinfunction "SCL_7") (pintype "passive"))
      (node (ref "U2") (pin "9") (pinfunction "I2CS_SCL_9") (pintype "input"))
    )
    (net (code "41") (name "Net-(C76-Pad1)") (class "Default")
      (node (ref "C76") (pin "1") (pinfunction "1_1") (pintype "passive"))
      (node (ref "R74") (pin "2") (pinfunction "2_2") (pintype "passive"))
    )
    (net (code "42") (name "Net-(C89-Pad1)") (class "Default")
      (node (ref "C89") (pin "1") (pinfunction "1_1") (pintype "passive"))
      (node (ref "R79") (pin "1") (pinfunction "1_1") (pintype "passive"))
    )
    (net (code "43") (name "Net-(D16-K)") (class "Default")
      (node (ref "C90") (pin "1") (pinfunction "1_1") (pintype "passive"))
      (node (ref "D16") (pin "1") (pinfunction "K_1") (pintype "passive"))
      (node (ref "R76") (pin "2") (pinfunction "2_2") (pintype "passive"))
      (node (ref "R81") (pin "1") (pinfunction "1_1") (pintype "passive"))
    )
    (net (code "44") (name "Net-(IC16-ATTACH)") (class "Default")
      (node (ref "IC16") (pin "11") (pinfunction "ATTACH_11") (pintype "passive"))
      (node (ref "J33") (pin "1") (pinfunction "1_1") (pintype "passive"))
    )
    (net (code "45") (name "Net-(IC16-GPIO)") (class "Default")
      (node (ref "IC16") (pin "15") (pinfunction "GPIO_15") (pintype "passive"))
      (node (ref "R77") (pin "2") (pinfunction "2_2") (pintype "passive"))
    )
    (net (code "46") (name "Net-(IC16-RESET)") (class "Default")
      (node (ref "IC16") (pin "6") (pinfunction "RESET_6") (pintype "passive"))
      (node (ref "R89") (pin "2") (pinfunction "2_2") (pintype "passive"))
    )
    (net (code "47") (name "Net-(IC16-VBUS_VS_DISCH)") (class "Default")
      (node (ref "IC16") (pin "18") (pinfunction "VBUS_VS_DISCH_18") (pintype "passive"))
      (node (ref "R81") (pin "2") (pinfunction "2_2") (pintype "passive"))
    )
    (net (code "48") (name "Net-(IC16-VREG_1V2)") (class "Default")
      (node (ref "C104") (pin "1") (pinfunction "1_1") (pintype "passive"))
      (node (ref "IC16") (pin "21") (pinfunction "VREG_1V2_21") (pintype "passive"))
    )
    (net (code "49") (name "Net-(IC16-VREG_2V7)") (class "Default")
      (node (ref "C106") (pin "1") (pinfunction "1_1") (pintype "passive"))
      (node (ref "IC16") (pin "23") (pinfunction "VREG_2V7_23") (pintype "passive"))
    )
    (net (code "50") (name "Net-(Q15-G)") (class "Default")
      (node (ref "Q15") (pin "1") (pinfunction "G_1") (pintype "passive"))
      (node (ref "R75") (pin "2") (pinfunction "2_2") (pintype "passive"))
      (node (ref "R79") (pin "2") (pinfunction "2_2") (pintype "passive"))
      (node (ref "R80") (pin "1") (pinfunction "1_1") (pintype "passive"))
    )
    (net (code "51") (name "Net-(U2-ADCIN2)") (class "Default")
      (node (ref "R83") (pin "2") (pinfunction "2_2") (pintype "passive"))
      (node (ref "U2") (pin "3") (pinfunction "ADCIN2_3") (pintype "input"))
    )
    (net (code "52") (name "Net-(U2-LDO_1V5)") (class "Default")
      (node (ref "C91") (pin "1") (pinfunction "1_1") (pintype "passive"))
      (node (ref "U2") (pin "4") (pinfunction "LDO_1V5_4") (pintype "output"))
    )
    (net (code "53") (name "Net-(U2-~{I2CS_IRQ})") (class "Default")
      (node (ref "R86") (pin "2") (pinfunction "2_2") (pintype "passive"))
      (node (ref "U2") (pin "10") (pinfunction "~{I2CS_IRQ}_10") (pintype "output"))
    )
    (net (code "54") (name "Net-(U3-SCL)") (class "Default")
      (node (ref "J34") (pin "1") (pinfunction "1_1") (pintype "passive"))
      (node (ref "R92") (pin "2") (pinfunction "2_2") (pintype "passive"))
      (node (ref "U3") (pin "6") (pinfunction "SCL_6") (pintype "passive"))
    )
    (net (code "55") (name "Net-(U3-SDA)") (class "Default")
      (node (ref "J35") (pin "1") (pinfunction "1_1") (pintype "passive"))
      (node (ref "R93") (pin "2") (pinfunction "2_2") (pintype "passive"))
      (node (ref "U3") (pin "5") (pinfunction "SDA_5") (pintype "passive"))
    )
    (net (code "56") (name "Net-(U3-VCC)") (class "Default")
      (node (ref "R90") (pin "2") (pinfunction "2_2") (pintype "passive"))
      (node (ref "R91") (pin "2") (pinfunction "2_2") (pintype "passive"))
      (node (ref "U3") (pin "8") (pinfunction "VCC_8") (pintype "passive"))
    )
    (net (code "57") (name "USB2_Bat_D_N") (class "Default")
      (node (ref "D14") (pin "1") (pinfunction "1_1") (pintype "passive"))
      (node (ref "J29") (pin "A7") (pinfunction "D-_A7") (pintype "passive"))
      (node (ref "J29") (pin "B7") (pinfunction "D-_B7") (pintype "passive"))
    )
    (net (code "58") (name "USB2_Bat_D_P") (class "Default")
      (node (ref "D15") (pin "1") (pinfunction "1_1") (pintype "passive"))
      (node (ref "J29") (pin "A6") (pinfunction "D+_A6") (pintype "passive"))
      (node (ref "J29") (pin "B6") (pinfunction "D+_B6") (pintype "passive"))
    )
    (net (code "59") (name "USB2_Power_D_N") (class "Default")
      (node (ref "D12") (pin "1") (pinfunction "1_1") (pintype "passive"))
      (node (ref "J28") (pin "A7") (pinfunction "D-_A7") (pintype "passive"))
      (node (ref "J28") (pin "B7") (pinfunction "D-_B7") (pintype "passive"))
    )
    (net (code "60") (name "USB2_Power_D_P") (class "Default")
      (node (ref "D13") (pin "1") (pinfunction "1_1") (pintype "passive"))
      (node (ref "J28") (pin "A6") (pinfunction "D+_A6") (pintype "passive"))
      (node (ref "J28") (pin "B6") (pinfunction "D+_B6") (pintype "passive"))
    )
    (net (code "61") (name "USB3-0-RX_N") (class "Default")
      (node (ref "IC14") (pin "16") (pinfunction "SSA1_(N)_16") (pintype "passive"))
    )
    (net (code "62") (name "USB3-0-RX_P") (class "Default")
      (node (ref "IC14") (pin "15") (pinfunction "SSA1_(P)_15") (pintype "passive"))
    )
    (net (code "63") (name "USB3-0-TX_N") (class "Default")
      (node (ref "IC14") (pin "12") (pinfunction "SSAO_(N)_12") (pintype "passive"))
    )
    (net (code "64") (name "USB3-0-TX_P") (class "Default")
      (node (ref "IC14") (pin "11") (pinfunction "SSAO_(P)_11") (pintype "passive"))
    )
    (net (code "65") (name "USB3-1-RX_N") (class "Default")
      (node (ref "IC15") (pin "16") (pinfunction "SSA1_(N)_16") (pintype "passive"))
    )
    (net (code "66") (name "USB3-1-RX_P") (class "Default")
      (node (ref "IC15") (pin "15") (pinfunction "SSA1_(P)_15") (pintype "passive"))
    )
    (net (code "67") (name "USB3-1-TX_N") (class "Default")
      (node (ref "IC15") (pin "12") (pinfunction "SSAO_(N)_12") (pintype "passive"))
    )
    (net (code "68") (name "USB3-1-TX_P") (class "Default")
      (node (ref "IC15") (pin "11") (pinfunction "SSAO_(P)_11") (pintype "passive"))
    )
    (net (code "69") (name "USB_PD_3V3") (class "Default")
      (node (ref "C97") (pin "1") (pinfunction "1_1") (pintype "passive"))
      (node (ref "R87") (pin "2") (pinfunction "2_2") (pintype "passive"))
      (node (ref "R88") (pin "2") (pinfunction "2_2") (pintype "passive"))
      (node (ref "R90") (pin "1") (pinfunction "1_1") (pintype "passive"))
      (node (ref "U2") (pin "1") (pinfunction "LDO_3V3_1") (pintype "output"))
      (node (ref "U2") (pin "2") (pinfunction "ADCIN1_2") (pintype "input"))
    )
    (net (code "70") (name "VCC_USB_Bat") (class "Default")
      (node (ref "C105") (pin "1") (pinfunction "1_1") (pintype "passive"))
      (node (ref "C73") (pin "1") (pinfunction "1_1") (pintype "passive"))
      (node (ref "C74") (pin "1") (pinfunction "1_1") (pintype "passive"))
      (node (ref "C77") (pin "2") (pinfunction "2_2") (pintype "passive"))
      (node (ref "C78") (pin "1") (pinfunction "1_1") (pintype "passive"))
      (node (ref "C79") (pin "1") (pinfunction "1_1") (pintype "passive"))
      (node (ref "D11") (pin "1") (pinfunction "K_1") (pintype "passive"))
      (node (ref "D16") (pin "2") (pinfunction "A_2") (pintype "passive"))
      (node (ref "IC16") (pin "24") (pinfunction "VDD_24") (pintype "passive"))
      (node (ref "J29") (pin "A4") (pinfunction "VBUS_A4") (pintype "passive"))
      (node (ref "J29") (pin "A9") (pinfunction "VBUS_A9") (pintype "passive"))
      (node (ref "J29") (pin "B4") (pinfunction "VBUS_B4") (pintype "passive"))
      (node (ref "J29") (pin "B9") (pinfunction "VBUS_B9") (pintype "passive"))
      (node (ref "Q15") (pin "2") (pinfunction "S_2") (pintype "passive"))
      (node (ref "R75") (pin "1") (pinfunction "1_1") (pintype "passive"))
      (node (ref "R76") (pin "1") (pinfunction "1_1") (pintype "passive"))
    )
    (net (code "71") (name "VCC_USB_Bat_Sink") (class "Default")
      (node (ref "C89") (pin "2") (pinfunction "2_2") (pintype "passive"))
      (node (ref "Q15") (pin "3") (pinfunction "D_3") (pintype "passive"))
    )
    (net (code "72") (name "VCC_USB_Power") (class "Default")
      (node (ref "C70") (pin "1") (pinfunction "1_1") (pintype "passive"))
      (node (ref "C71") (pin "1") (pinfunction "1_1") (pintype "passive"))
      (node (ref "C72") (pin "1") (pinfunction "1_1") (pintype "passive"))
      (node (ref "C75") (pin "1") (pinfunction "1_1") (pintype "passive"))
      (node (ref "C76") (pin "2") (pinfunction "2_2") (pintype "passive"))
      (node (ref "C80") (pin "1") (pinfunction "1_1") (pintype "passive"))
      (node (ref "C92") (pin "1") (pinfunction "1_1") (pintype "passive"))
      (node (ref "C93") (pin "1") (pinfunction "1_1") (pintype "passive"))
      (node (ref "C94") (pin "1") (pinfunction "1_1") (pintype "passive"))
      (node (ref "C95") (pin "1") (pinfunction "1_1") (pintype "passive"))
      (node (ref "C96") (pin "1") (pinfunction "1_1") (pintype "passive"))
      (node (ref "D10") (pin "1") (pinfunction "K_1") (pintype "passive"))
      (node (ref "J28") (pin "A4") (pinfunction "VBUS_A4") (pintype "passive"))
      (node (ref "J28") (pin "A9") (pinfunction "VBUS_A9") (pintype "passive"))
      (node (ref "J28") (pin "B4") (pinfunction "VBUS_B4") (pintype "passive"))
      (node (ref "J28") (pin "B9") (pinfunction "VBUS_B9") (pintype "passive"))
      (node (ref "U2") (pin "23_25") (pinfunction "VBUS_IN_23_25") (pintype "input"))
      (node (ref "U2") (pin "32_33") (pinfunction "VBUS_32_33") (pintype "input"))
    )
    (net (code "73") (name "unconnected-(IC14-HSA_(N)-Pad7)") (class "Default")
      (node (ref "IC14") (pin "7") (pinfunction "HSA_(N)_7") (pintype "passive+no_connect"))
    )
    (net (code "74") (name "unconnected-(IC14-HSA_(P)-Pad8)") (class "Default")
      (node (ref "IC14") (pin "8") (pinfunction "HSA_(P)_8") (pintype "passive+no_connect"))
    )
    (net (code "75") (name "unconnected-(IC14-HSB_(N)-Pad32)") (class "Default")
      (node (ref "IC14") (pin "32") (pinfunction "HSB_(N)_32") (pintype "passive+no_connect"))
    )
    (net (code "76") (name "unconnected-(IC14-HSB_(P)-Pad31)") (class "Default")
      (node (ref "IC14") (pin "31") (pinfunction "HSB_(P)_31") (pintype "passive+no_connect"))
    )
    (net (code "77") (name "unconnected-(IC14-HSC(N)-Pad34)") (class "Default")
      (node (ref "IC14") (pin "34") (pinfunction "HSC(N)_34") (pintype "passive+no_connect"))
    )
    (net (code "78") (name "unconnected-(IC14-HSC_(P)-Pad33)") (class "Default")
      (node (ref "IC14") (pin "33") (pinfunction "HSC_(P)_33") (pintype "passive+no_connect"))
    )
    (net (code "79") (name "unconnected-(IC14-NC_1-Pad1)") (class "Default")
      (node (ref "IC14") (pin "1") (pinfunction "NC_1_1") (pintype "passive+no_connect"))
    )
    (net (code "80") (name "unconnected-(IC14-NC_2-Pad2)") (class "Default")
      (node (ref "IC14") (pin "2") (pinfunction "NC_2_2") (pintype "passive+no_connect"))
    )
    (net (code "81") (name "unconnected-(IC14-NC_3-Pad3)") (class "Default")
      (node (ref "IC14") (pin "3") (pinfunction "NC_3_3") (pintype "passive+no_connect"))
    )
    (net (code "82") (name "unconnected-(IC14-NC_4-Pad4)") (class "Default")
      (node (ref "IC14") (pin "4") (pinfunction "NC_4_4") (pintype "passive+no_connect"))
    )
    (net (code "83") (name "unconnected-(IC14-NC_5-Pad5)") (class "Default")
      (node (ref "IC14") (pin "5") (pinfunction "NC_5_5") (pintype "passive+no_connect"))
    )
    (net (code "84") (name "unconnected-(IC14-NC_6-Pad18)") (class "Default")
      (node (ref "IC14") (pin "18") (pinfunction "NC_6_18") (pintype "passive+no_connect"))
    )
    (net (code "85") (name "unconnected-(IC14-NC_7-Pad35)") (class "Default")
      (node (ref "IC14") (pin "35") (pinfunction "NC_7_35") (pintype "passive+no_connect"))
    )
    (net (code "86") (name "unconnected-(IC14-NC_8-Pad36)") (class "Default")
      (node (ref "IC14") (pin "36") (pinfunction "NC_8_36") (pintype "passive+no_connect"))
    )
    (net (code "87") (name "unconnected-(IC14-NC_9-Pad37)") (class "Default")
      (node (ref "IC14") (pin "37") (pinfunction "NC_9_37") (pintype "passive+no_connect"))
    )
    (net (code "88") (name "unconnected-(IC14-NC_10-Pad38)") (class "Default")
      (node (ref "IC14") (pin "38") (pinfunction "NC_10_38") (pintype "passive+no_connect"))
    )
    (net (code "89") (name "unconnected-(IC14-NC_11-Pad39)") (class "Default")
      (node (ref "IC14") (pin "39") (pinfunction "NC_11_39") (pintype "passive+no_connect"))
    )
    (net (code "90") (name "unconnected-(IC14-NC_12-Pad40)") (class "Default")
      (node (ref "IC14") (pin "40") (pinfunction "NC_12_40") (pintype "passive+no_connect"))
    )
    (net (code "91") (name "unconnected-(IC14-NC_13-Pad41)") (class "Default")
      (node (ref "IC14") (pin "41") (pinfunction "NC_13_41") (pintype "passive+no_connect"))
    )
    (net (code "92") (name "unconnected-(IC14-NC_14-Pad42)") (class "Default")
      (node (ref "IC14") (pin "42") (pinfunction "NC_14_42") (pintype "passive+no_connect"))
    )
    (net (code "93") (name "unconnected-(IC15-HSA_(N)-Pad7)") (class "Default")
      (node (ref "IC15") (pin "7") (pinfunction "HSA_(N)_7") (pintype "passive+no_connect"))
    )
    (net (code "94") (name "unconnected-(IC15-HSA_(P)-Pad8)") (class "Default")
      (node (ref "IC15") (pin "8") (pinfunction "HSA_(P)_8") (pintype "passive+no_connect"))
    )
    (net (code "95") (name "unconnected-(IC15-HSB_(N)-Pad32)") (class "Default")
      (node (ref "IC15") (pin "32") (pinfunction "HSB_(N)_32") (pintype "passive+no_connect"))
    )
    (net (code "96") (name "unconnected-(IC15-HSB_(P)-Pad31)") (class "Default")
      (node (ref "IC15") (pin "31") (pinfunction "HSB_(P)_31") (pintype "passive+no_connect"))
    )
    (net (code "97") (name "unconnected-(IC15-HSC(N)-Pad34)") (class "Default")
      (node (ref "IC15") (pin "34") (pinfunction "HSC(N)_34") (pintype "passive+no_connect"))
    )
    (net (code "98") (name "unconnected-(IC15-HSC_(P)-Pad33)") (class "Default")
      (node (ref "IC15") (pin "33") (pinfunction "HSC_(P)_33") (pintype "passive+no_connect"))
    )
    (net (code "99") (name "unconnected-(IC15-NC_1-Pad1)") (class "Default")
      (node (ref "IC15") (pin "1") (pinfunction "NC_1_1") (pintype "passive+no_connect"))
    )
    (net (code "100") (name "unconnected-(IC15-NC_2-Pad2)") (class "Default")
      (node (ref "IC15") (pin "2") (pinfunction "NC_2_2") (pintype "passive+no_connect"))
    )
    (net (code "101") (name "unconnected-(IC15-NC_3-Pad3)") (class "Default")
      (node (ref "IC15") (pin "3") (pinfunction "NC_3_3") (pintype "passive+no_connect"))
    )
    (net (code "102") (name "unconnected-(IC15-NC_4-Pad4)") (class "Default")
      (node (ref "IC15") (pin "4") (pinfunction "NC_4_4") (pintype "passive+no_connect"))
    )
    (net (code "103") (name "unconnected-(IC15-NC_5-Pad5)") (class "Default")
      (node (ref "IC15") (pin "5") (pinfunction "NC_5_5") (pintype "passive+no_connect"))
    )
    (net (code "104") (name "unconnected-(IC15-NC_6-Pad18)") (class "Default")
      (node (ref "IC15") (pin "18") (pinfunction "NC_6_18") (pintype "passive+no_connect"))
    )
    (net (code "105") (name "unconnected-(IC15-NC_7-Pad35)") (class "Default")
      (node (ref "IC15") (pin "35") (pinfunction "NC_7_35") (pintype "passive+no_connect"))
    )
    (net (code "106") (name "unconnected-(IC15-NC_8-Pad36)") (class "Default")
      (node (ref "IC15") (pin "36") (pinfunction "NC_8_36") (pintype "passive+no_connect"))
    )
    (net (code "107") (name "unconnected-(IC15-NC_9-Pad37)") (class "Default")
      (node (ref "IC15") (pin "37") (pinfunction "NC_9_37") (pintype "passive+no_connect"))
    )
    (net (code "108") (name "unconnected-(IC15-NC_10-Pad38)") (class "Default")
      (node (ref "IC15") (pin "38") (pinfunction "NC_10_38") (pintype "passive+no_connect"))
    )
    (net (code "109") (name "unconnected-(IC15-NC_11-Pad39)") (class "Default")
      (node (ref "IC15") (pin "39") (pinfunction "NC_11_39") (pintype "passive+no_connect"))
    )
    (net (code "110") (name "unconnected-(IC15-NC_12-Pad40)") (class "Default")
      (node (ref "IC15") (pin "40") (pinfunction "NC_12_40") (pintype "passive+no_connect"))
    )
    (net (code "111") (name "unconnected-(IC15-NC_13-Pad41)") (class "Default")
      (node (ref "IC15") (pin "41") (pinfunction "NC_13_41") (pintype "passive+no_connect"))
    )
    (net (code "112") (name "unconnected-(IC15-NC_14-Pad42)") (class "Default")
      (node (ref "IC15") (pin "42") (pinfunction "NC_14_42") (pintype "passive+no_connect"))
    )
    (net (code "113") (name "unconnected-(IC16-DISCH-Pad9)") (class "Default")
      (node (ref "IC16") (pin "9") (pinfunction "DISCH_9") (pintype "passive+no_connect"))
    )
    (net (code "114") (name "unconnected-(IC16-NC-Pad3)") (class "Default")
      (node (ref "IC16") (pin "3") (pinfunction "NC_3") (pintype "passive+no_connect"))
    )
    (net (code "115") (name "unconnected-(J28-SBU1-PadA8)") (class "Default")
      (node (ref "J28") (pin "A8") (pinfunction "SBU1_A8") (pintype "passive+no_connect"))
    )
    (net (code "116") (name "unconnected-(J28-SBU2-PadB8)") (class "Default")
      (node (ref "J28") (pin "B8") (pinfunction "SBU2_B8") (pintype "passive+no_connect"))
    )
    (net (code "117") (name "unconnected-(J29-SBU1-PadA8)") (class "Default")
      (node (ref "J29") (pin "A8") (pinfunction "SBU1_A8") (pintype "passive+no_connect"))
    )
    (net (code "118") (name "unconnected-(J29-SBU2-PadB8)") (class "Default")
      (node (ref "J29") (pin "B8") (pinfunction "SBU2_B8") (pintype "passive+no_connect"))
    )
    (net (code "119") (name "unconnected-(U2-GPIO6-Pad37)") (class "Default")
      (node (ref "U2") (pin "37") (pinfunction "GPIO6_37") (pintype "output"))
    )
    (net (code "120") (name "unconnected-(U2-GPIO7-Pad36)") (class "Default")
      (node (ref "U2") (pin "36") (pinfunction "GPIO7_36") (pintype "output"))
    )
    (net (code "121") (name "unconnected-(U2-GPIO11-Pad13)") (class "Default")
      (node (ref "U2") (pin "13") (pinfunction "GPIO11_13") (pintype "output"))
    )
  )
)
